# power.net
KiCad netlist of a schematic drawn in Altium Designer
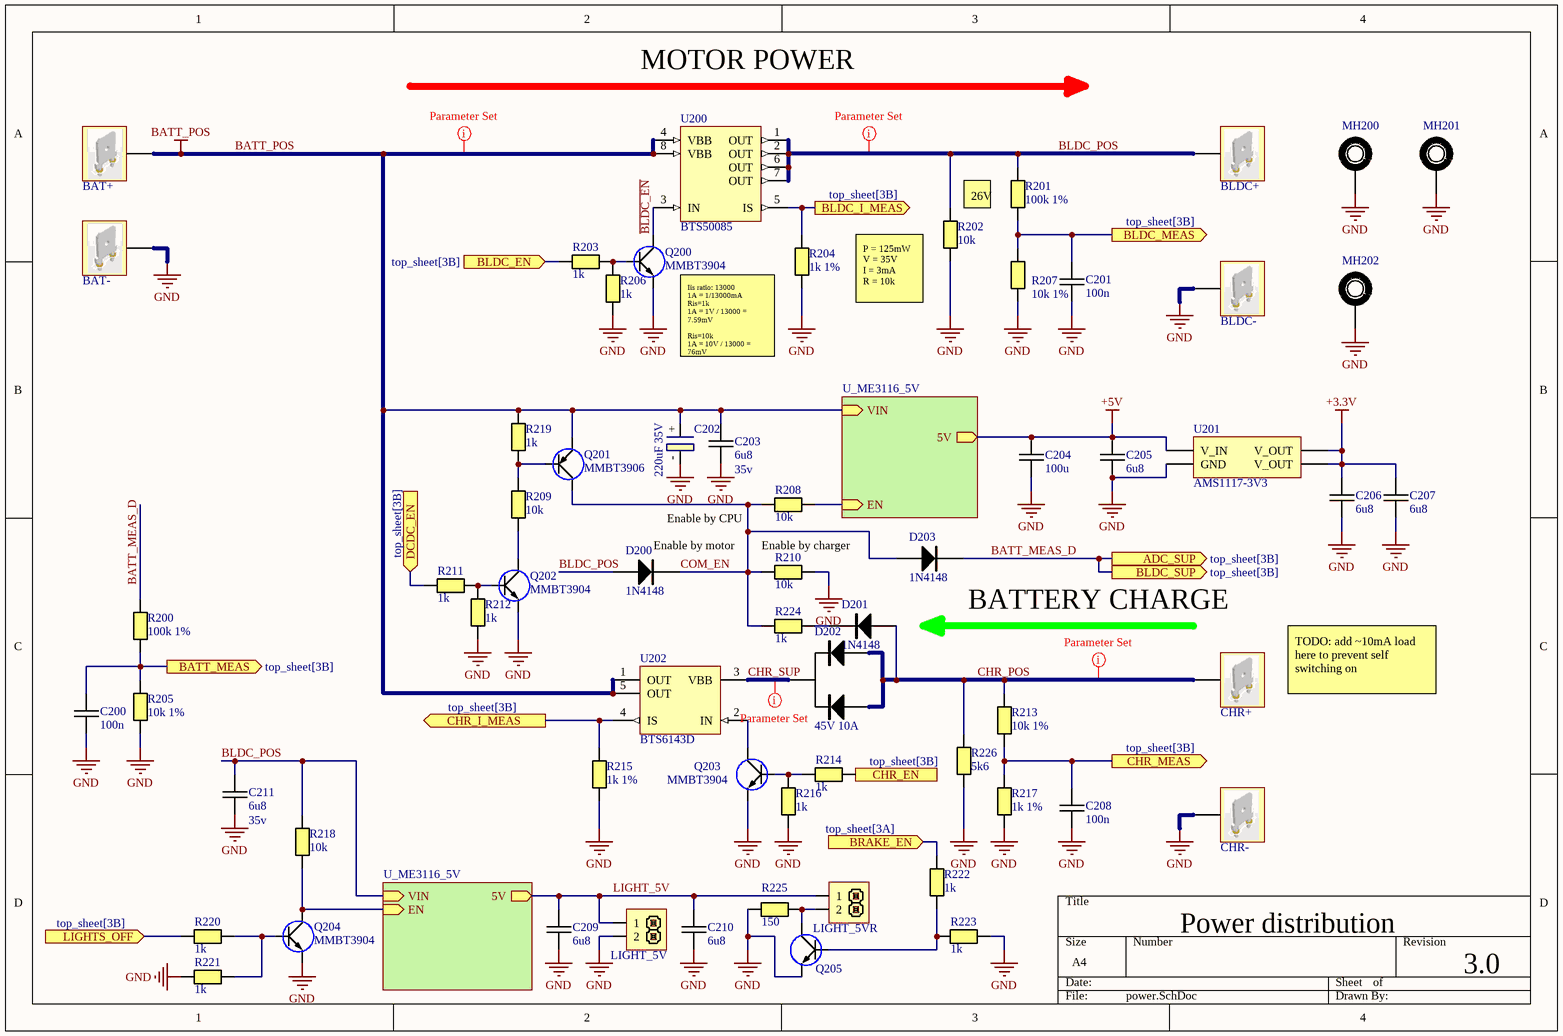
[diagram p0: power.SchDoc]

(export (version "E")
  (design (tool "Eeschema 10.0.6"))
  (components
    (comp (ref "BAT+")
      (value "Crimp 6.3 single PCB")
      (footprint "Crimp 6.3mm single PCB")
      (description "Straight Mount Angle PCB Tab Terminal")
      (libsource (lib "Connectors") (part "Crimp 6.3 single PCB"))
    )
    (comp (ref "BAT-")
      (value "Crimp 6.3 single PCB")
      (footprint "Crimp 6.3mm single PCB")
      (description "Straight Mount Angle PCB Tab Terminal")
      (libsource (lib "Connectors") (part "Crimp 6.3 single PCB"))
    )
    (comp (ref "BLDC+")
      (value "Crimp 6.3 single PCB")
      (footprint "Crimp 6.3mm single PCB")
      (description "Straight Mount Angle PCB Tab Terminal")
      (libsource (lib "") (part "Crimp 6.3 single PCB_1"))
    )
    (comp (ref "BLDC-")
      (value "Crimp 6.3 single PCB")
      (footprint "Crimp 6.3mm single PCB")
      (description "Straight Mount Angle PCB Tab Terminal")
      (libsource (lib "") (part "Crimp 6.3 single PCB_1"))
    )
    (comp (ref "C200")
      (value "100n")
      (footprint "CAPC0603(1608)55_N")
      (description "Ceramic capacitor Medium density")
      (libsource (lib "Discrete") (part "Capacitor M"))
    )
    (comp (ref "C201")
      (value "100n")
      (footprint "CAPC0603(1608)55_N")
      (description "Ceramic capacitor Medium density")
      (libsource (lib "Discrete") (part "Capacitor M"))
    )
    (comp (ref "C202")
      (value "220uF 35V")
      (footprint "10x10.5 Capacitor")
      (description "Capacitor Electrolitic")
      (libsource (lib "Discrete") (part "Capacitor Electrolitic"))
    )
    (comp (ref "C203")
      (value "6u8")
      (footprint "CAPC0805(2012)75_N")
      (description "Ceramic capacitor Medium density")
      (fields (field (name "VMAX") "35v"))
      (libsource (lib "Discrete") (part "Capacitor M"))
    )
    (comp (ref "C204")
      (value "100u")
      (footprint "CAPC1206(3216)75_N")
      (description "Ceramic capacitor Medium density")
      (libsource (lib "Discrete") (part "Capacitor M"))
    )
    (comp (ref "C205")
      (value "6u8")
      (footprint "CAPC0805(2012)75_N")
      (description "Ceramic capacitor Medium density")
      (libsource (lib "Discrete") (part "Capacitor M"))
    )
    (comp (ref "C206")
      (value "6u8")
      (footprint "CAPC0805(2012)75_N")
      (description "Ceramic capacitor Medium density")
      (libsource (lib "Discrete") (part "Capacitor M"))
    )
    (comp (ref "C207")
      (value "6u8")
      (footprint "CAPC0805(2012)75_N")
      (description "Ceramic capacitor Medium density")
      (libsource (lib "Discrete") (part "Capacitor M"))
    )
    (comp (ref "C208")
      (value "100n")
      (footprint "CAPC0603(1608)55_N")
      (description "Ceramic capacitor Medium density")
      (libsource (lib "Discrete") (part "Capacitor M"))
    )
    (comp (ref "C209")
      (value "6u8")
      (footprint "CAPC0805(2012)75_N")
      (description "Ceramic capacitor Medium density")
      (libsource (lib "Discrete") (part "Capacitor M"))
    )
    (comp (ref "C210")
      (value "6u8")
      (footprint "CAPC0805(2012)75_N")
      (description "Ceramic capacitor Medium density")
      (libsource (lib "Discrete") (part "Capacitor M"))
    )
    (comp (ref "C211")
      (value "6u8")
      (footprint "CAPC0805(2012)75_N")
      (description "Ceramic capacitor Medium density")
      (fields (field (name "VMAX") "35v"))
      (libsource (lib "Discrete") (part "Capacitor M"))
    )
    (comp (ref "CHR+")
      (value "Crimp 6.3 single PCB")
      (footprint "Crimp 6.3mm single PCB")
      (description "Straight Mount Angle PCB Tab Terminal")
      (libsource (lib "") (part "Crimp 6.3 single PCB_1"))
    )
    (comp (ref "CHR-")
      (value "Crimp 6.3 single PCB")
      (footprint "Crimp 6.3mm single PCB")
      (description "Straight Mount Angle PCB Tab Terminal")
      (libsource (lib "") (part "Crimp 6.3 single PCB_1"))
    )
    (comp (ref "CN200")
      (value "PIN HEADER 1x2")
      (footprint "XH2.54 2P")
      (description "LIGHT_5V")
      (fields (field (name "PARAMETER 1") "LIGHT_5V"))
      (libsource (lib "Connectors") (part "PIN HEADER 2.54 1x2"))
    )
    (comp (ref "CN201")
      (value "PIN HEADER 1x2")
      (footprint "XH2.54 2P")
      (description "LIGHT_5V")
      (fields (field (name "PARAMETER 1") "LIGHT_5VR"))
      (libsource (lib "Connectors") (part "PIN HEADER 2.54 1x2"))
    )
    (comp (ref "D200")
      (value "1N4148")
      (footprint "SOD80")
      (description "Small Signal Fast Switching Diodes")
      (libsource (lib "Diodes") (part "1N4148"))
    )
    (comp (ref "D201")
      (value "1N4148")
      (footprint "SOD80")
      (description "Small Signal Fast Switching Diodes")
      (libsource (lib "Diodes") (part "1N4148"))
    )
    (comp (ref "D202")
      (value "45V 10A")
      (footprint "DPAK")
      (description "Power schottky rectifier")
      (libsource (lib "Diodes") (part "STPS1045B"))
    )
    (comp (ref "D203")
      (value "1N4148")
      (footprint "SOD80")
      (description "Small Signal Fast Switching Diodes")
      (libsource (lib "Diodes") (part "1N4148"))
    )
    (comp (ref "MH200")
      (value "Mounting Hole")
      (footprint "MH_M3")
      (libsource (lib "Connectors") (part "Mounting Hole"))
    )
    (comp (ref "MH201")
      (value "Mounting Hole")
      (footprint "MH_M3")
      (libsource (lib "Connectors") (part "Mounting Hole"))
    )
    (comp (ref "MH202")
      (value "Mounting Hole")
      (footprint "MH_M3")
      (libsource (lib "Connectors") (part "Mounting Hole"))
    )
    (comp (ref "Q200")
      (value "MMBT3904")
      (footprint "SOT23")
      (description "NPN General Purpose Transistor")
      (libsource (lib "Transistors") (part "2N3904"))
    )
    (comp (ref "Q201")
      (value "MMBT3906")
      (footprint "SOT23")
      (description "PNP General Purpose Transistor")
      (libsource (lib "Transistors") (part "2N3906"))
    )
    (comp (ref "Q202")
      (value "MMBT3904")
      (footprint "SOT23")
      (description "NPN General Purpose Transistor")
      (libsource (lib "Transistors") (part "2N3904"))
    )
    (comp (ref "Q203")
      (value "MMBT3904")
      (footprint "SOT23")
      (description "NPN General Purpose Transistor")
      (libsource (lib "Transistors") (part "2N3904"))
    )
    (comp (ref "Q204")
      (value "MMBT3904")
      (footprint "SOT23")
      (description "NPN General Purpose Transistor")
      (libsource (lib "Transistors") (part "2N3904"))
    )
    (comp (ref "Q205")
      (value "MMBT3904")
      (footprint "SOT23")
      (description "NPN General Purpose Transistor")
      (libsource (lib "Transistors") (part "2N3904"))
    )
    (comp (ref "R200")
      (value "100k 1%")
      (footprint "RESC0603(1608)_N")
      (description "Resistor Medium Density")
      (libsource (lib "Discrete") (part "Resistor M"))
    )
    (comp (ref "R201")
      (value "100k 1%")
      (footprint "RESC0603(1608)_N")
      (description "Resistor Medium Density")
      (libsource (lib "Discrete") (part "Resistor M"))
    )
    (comp (ref "R202")
      (value "10k")
      (footprint "RESC0805(2012)_N")
      (description "Resistor Medium Density")
      (libsource (lib "Discrete") (part "Resistor M"))
    )
    (comp (ref "R203")
      (value "1k")
      (footprint "RESC0603(1608)_N")
      (description "Resistor Medium Density")
      (libsource (lib "") (part "Resistor M_1"))
    )
    (comp (ref "R204")
      (value "1k 1%")
      (footprint "RESC0603(1608)_N")
      (description "Resistor Medium Density")
      (libsource (lib "Discrete") (part "Resistor M"))
    )
    (comp (ref "R205")
      (value "10k 1%")
      (footprint "RESC0603(1608)_N")
      (description "Resistor Medium Density")
      (libsource (lib "Discrete") (part "Resistor M"))
    )
    (comp (ref "R206")
      (value "1k")
      (footprint "RESC0603(1608)_N")
      (description "Resistor Medium Density")
      (libsource (lib "Discrete") (part "Resistor M"))
    )
    (comp (ref "R207")
      (value "10k 1%")
      (footprint "RESC0603(1608)_N")
      (description "Resistor Medium Density")
      (libsource (lib "Discrete") (part "Resistor M"))
    )
    (comp (ref "R208")
      (value "10k")
      (footprint "RESC0603(1608)_N")
      (description "Resistor Medium Density")
      (libsource (lib "") (part "Resistor M_2"))
    )
    (comp (ref "R209")
      (value "10k")
      (footprint "RESC0603(1608)_N")
      (description "Resistor Medium Density")
      (libsource (lib "") (part "Resistor M_3"))
    )
    (comp (ref "R210")
      (value "10k")
      (footprint "RESC0603(1608)_N")
      (description "Resistor Medium Density")
      (libsource (lib "") (part "Resistor M_1"))
    )
    (comp (ref "R211")
      (value "1k")
      (footprint "RESC0603(1608)_N")
      (description "Resistor Medium Density")
      (libsource (lib "") (part "Resistor M_1"))
    )
    (comp (ref "R212")
      (value "1k")
      (footprint "RESC0603(1608)_N")
      (description "Resistor Medium Density")
      (libsource (lib "Discrete") (part "Resistor M"))
    )
    (comp (ref "R213")
      (value "10k 1%")
      (footprint "RESC0603(1608)_N")
      (description "Resistor Medium Density")
      (libsource (lib "Discrete") (part "Resistor M"))
    )
    (comp (ref "R214")
      (value "1k")
      (footprint "RESC0603(1608)_N")
      (description "Resistor Medium Density")
      (libsource (lib "") (part "Resistor M_3"))
    )
    (comp (ref "R215")
      (value "1k 1%")
      (footprint "RESC0603(1608)_N")
      (description "Resistor Medium Density")
      (libsource (lib "Discrete") (part "Resistor M"))
    )
    (comp (ref "R216")
      (value "1k")
      (footprint "RESC0603(1608)_N")
      (description "Resistor Medium Density")
      (libsource (lib "Discrete") (part "Resistor M"))
    )
    (comp (ref "R217")
      (value "1k 1%")
      (footprint "RESC0603(1608)_N")
      (description "Resistor Medium Density")
      (libsource (lib "Discrete") (part "Resistor M"))
    )
    (comp (ref "R218")
      (value "10k")
      (footprint "RESC0603(1608)_N")
      (description "Resistor Medium Density")
      (libsource (lib "Discrete") (part "Resistor M"))
    )
    (comp (ref "R219")
      (value "1k")
      (footprint "RESC0603(1608)_N")
      (description "Resistor Medium Density")
      (libsource (lib "Discrete") (part "Resistor M"))
    )
    (comp (ref "R220")
      (value "1k")
      (footprint "RESC0603(1608)_N")
      (description "Resistor Medium Density")
      (libsource (lib "") (part "Resistor M_2"))
    )
    (comp (ref "R221")
      (value "1k")
      (footprint "RESC0603(1608)_N")
      (description "Resistor Medium Density")
      (libsource (lib "") (part "Resistor M_2"))
    )
    (comp (ref "R222")
      (value "1k")
      (footprint "RESC0603(1608)_N")
      (description "Resistor Medium Density")
      (libsource (lib "") (part "Resistor M_2"))
    )
    (comp (ref "R223")
      (value "1k")
      (footprint "RESC0603(1608)_N")
      (description "Resistor Medium Density")
      (libsource (lib "") (part "Resistor M_2"))
    )
    (comp (ref "R224")
      (value "1k")
      (footprint "RESC0603(1608)_N")
      (description "Resistor Medium Density")
      (libsource (lib "") (part "Resistor M_2"))
    )
    (comp (ref "R225")
      (value "150")
      (footprint "RESC0805(2012)_N")
      (description "Resistor Medium Density")
      (libsource (lib "") (part "Resistor M_1"))
    )
    (comp (ref "R226")
      (value "5k6")
      (footprint "RESC1206(3216)_N")
      (description "Resistor Medium Density")
      (libsource (lib "Discrete") (part "Resistor M"))
    )
    (comp (ref "U200")
      (value "BTS50085")
      (footprint "PG-TO220-7-4")
      (description "Smart Highside High Current Power Switch")
      (libsource (lib "Switches") (part "BTS50085-1TMA"))
    )
    (comp (ref "U201")
      (value "AMS1117-3V3")
      (footprint "SOT229P700X180-4N")
      (description "800mA LDO  15V max")
      (libsource (lib "VoltageRegulators") (part "AMS1117"))
    )
    (comp (ref "U202")
      (value "BTS6143D")
      (footprint "ITO252-5-11_M")
      (fields (field (name "MANUFACTURER") "Infineon"))
      (libsource (lib "Switches") (part "BTS6143D"))
    )
  )
  (nets
    (net (code "1") (name "+3.3V") (class "Default")
      (node (ref "C206") (pin "1") (pinfunction "1_1") (pintype "passive"))
      (node (ref "C207") (pin "1") (pinfunction "1_1") (pintype "passive"))
      (node (ref "U201") (pin "2") (pinfunction "V_OUT_2") (pintype "passive"))
      (node (ref "U201") (pin "4") (pinfunction "V_OUT_4") (pintype "passive"))
    )
    (net (code "2") (name "+5V") (class "Default")
      (node (ref "C204") (pin "1") (pinfunction "1_1") (pintype "passive"))
      (node (ref "C205") (pin "1") (pinfunction "1_1") (pintype "passive"))
      (node (ref "U201") (pin "3") (pinfunction "V_IN_3") (pintype "passive"))
    )
    (net (code "3") (name "/BATT_MEAS") (class "Default")
      (node (ref "C200") (pin "1") (pinfunction "1_1") (pintype "passive"))
      (node (ref "R200") (pin "1") (pinfunction "1_1") (pintype "passive"))
      (node (ref "R205") (pin "2") (pinfunction "2_2") (pintype "passive"))
    )
    (net (code "4") (name "/BATT_MEAS_D") (class "Default")
      (node (ref "D203") (pin "2") (pinfunction "K_2") (pintype "passive"))
      (node (ref "R200") (pin "2") (pinfunction "2_2") (pintype "passive"))
    )
    (net (code "5") (name "/BLDC_EN") (class "Default")
      (node (ref "R203") (pin "1") (pinfunction "1_1") (pintype "passive"))
    )
    (net (code "6") (name "/BLDC_I_MEAS") (class "Default")
      (node (ref "R204") (pin "2") (pinfunction "2_2") (pintype "passive"))
      (node (ref "U200") (pin "5") (pinfunction "IS_5") (pintype "output"))
    )
    (net (code "7") (name "/BLDC_MEAS") (class "Default")
      (node (ref "C201") (pin "1") (pinfunction "1_1") (pintype "passive"))
      (node (ref "R201") (pin "1") (pinfunction "1_1") (pintype "passive"))
      (node (ref "R207") (pin "2") (pinfunction "2_2") (pintype "passive"))
    )
    (net (code "8") (name "/BLDC_POS") (class "Default")
      (node (ref "BLDC+") (pin "1") (pintype "passive"))
      (node (ref "C211") (pin "1") (pinfunction "1_1") (pintype "passive"))
      (node (ref "D200") (pin "1") (pinfunction "A_1") (pintype "passive"))
      (node (ref "R201") (pin "2") (pinfunction "2_2") (pintype "passive"))
      (node (ref "R202") (pin "2") (pinfunction "2_2") (pintype "passive"))
      (node (ref "R218") (pin "2") (pinfunction "2_2") (pintype "passive"))
      (node (ref "U200") (pin "1") (pinfunction "OUT_1") (pintype "output"))
      (node (ref "U200") (pin "2") (pinfunction "OUT_2") (pintype "output"))
      (node (ref "U200") (pin "6") (pinfunction "OUT_6") (pintype "output"))
      (node (ref "U200") (pin "7") (pinfunction "OUT_7") (pintype "output"))
    )
    (net (code "9") (name "/BRAKE_EN") (class "Default")
      (node (ref "R222") (pin "1") (pinfunction "1_1") (pintype "passive"))
    )
    (net (code "10") (name "/CHR_EN") (class "Default")
      (node (ref "R214") (pin "1") (pinfunction "1_1") (pintype "passive"))
    )
    (net (code "11") (name "/CHR_I_MEAS") (class "Default")
      (node (ref "R215") (pin "2") (pinfunction "2_2") (pintype "passive"))
      (node (ref "U202") (pin "4") (pinfunction "IS_4") (pintype "output"))
    )
    (net (code "12") (name "/CHR_MEAS") (class "Default")
      (node (ref "C208") (pin "1") (pinfunction "1_1") (pintype "passive"))
      (node (ref "R213") (pin "1") (pinfunction "1_1") (pintype "passive"))
      (node (ref "R217") (pin "2") (pinfunction "2_2") (pintype "passive"))
    )
    (net (code "13") (name "/CHR_POS") (class "Default")
      (node (ref "CHR+") (pin "1") (pintype "passive"))
      (node (ref "D201") (pin "1") (pinfunction "A_1") (pintype "passive"))
      (node (ref "D202") (pin "1") (pinfunction "A1_1") (pintype "passive"))
      (node (ref "D202") (pin "3") (pinfunction "A2_3") (pintype "passive"))
      (node (ref "R213") (pin "2") (pinfunction "2_2") (pintype "passive"))
      (node (ref "R226") (pin "2") (pinfunction "2_2") (pintype "passive"))
    )
    (net (code "14") (name "/CHR_SUP") (class "Default")
      (node (ref "D202") (pin "2") (pinfunction "K_2") (pintype "passive"))
      (node (ref "U202") (pin "3") (pinfunction "VBB_3") (pintype "power_in"))
    )
    (net (code "15") (name "/COM_EN") (class "Default")
      (node (ref "D200") (pin "2") (pinfunction "K_2") (pintype "passive"))
      (node (ref "D203") (pin "1") (pinfunction "A_1") (pintype "passive"))
      (node (ref "Q201") (pin "3") (pinfunction "C_3") (pintype "passive"))
      (node (ref "R208") (pin "2") (pinfunction "2_2") (pintype "passive"))
      (node (ref "R210") (pin "1") (pinfunction "1_1") (pintype "passive"))
      (node (ref "R224") (pin "2") (pinfunction "2_2") (pintype "passive"))
    )
    (net (code "16") (name "/DCDC_EN") (class "Default")
      (node (ref "R211") (pin "1") (pinfunction "1_1") (pintype "passive"))
    )
    (net (code "17") (name "/EN") (class "Default")
      (node (ref "Q204") (pin "3") (pinfunction "C_3") (pintype "passive"))
      (node (ref "R218") (pin "1") (pinfunction "1_1") (pintype "passive"))
    )
    (net (code "18") (name "/EN_1") (class "Default")
      (node (ref "R208") (pin "1") (pinfunction "1_1") (pintype "passive"))
    )
    (net (code "19") (name "/LIGHTS_OFF") (class "Default")
      (node (ref "R220") (pin "2") (pinfunction "2_2") (pintype "passive"))
    )
    (net (code "20") (name "/LIGHT_5V") (class "Default")
      (node (ref "C209") (pin "1") (pinfunction "1_1") (pintype "passive"))
      (node (ref "C210") (pin "1") (pinfunction "1_1") (pintype "passive"))
      (node (ref "CN200") (pin "1") (pinfunction "1_1") (pintype "passive"))
      (node (ref "CN201") (pin "1") (pinfunction "1_1") (pintype "passive"))
    )
    (net (code "21") (name "/~{BLDC_EN}") (class "Default")
      (node (ref "Q200") (pin "3") (pinfunction "C_3") (pintype "passive"))
      (node (ref "U200") (pin "3") (pinfunction "IN_3") (pintype "input"))
    )
    (net (code "22") (name "BATT_POS") (class "Default")
      (node (ref "BAT+") (pin "1") (pintype "passive"))
      (node (ref "C202") (pin "+") (pinfunction "+_+") (pintype "passive"))
      (node (ref "C203") (pin "2") (pinfunction "2_2") (pintype "passive"))
      (node (ref "Q201") (pin "2") (pinfunction "E_2") (pintype "passive"))
      (node (ref "R219") (pin "2") (pinfunction "2_2") (pintype "passive"))
      (node (ref "U200") (pin "4") (pinfunction "VBB_4") (pintype "input"))
      (node (ref "U200") (pin "8") (pinfunction "VBB_8") (pintype "input"))
      (node (ref "U202") (pin "1") (pinfunction "OUT_1") (pintype "tri_state"))
      (node (ref "U202") (pin "5") (pinfunction "OUT_5") (pintype "tri_state"))
    )
    (net (code "23") (name "GND") (class "Default")
      (node (ref "BAT-") (pin "1") (pintype "passive"))
      (node (ref "BLDC-") (pin "1") (pintype "passive"))
      (node (ref "C200") (pin "2") (pinfunction "2_2") (pintype "passive"))
      (node (ref "C201") (pin "2") (pinfunction "2_2") (pintype "passive"))
      (node (ref "C202") (pin "-") (pinfunction "-_-") (pintype "passive"))
      (node (ref "C203") (pin "1") (pinfunction "1_1") (pintype "passive"))
      (node (ref "C204") (pin "2") (pinfunction "2_2") (pintype "passive"))
      (node (ref "C205") (pin "2") (pinfunction "2_2") (pintype "passive"))
      (node (ref "C206") (pin "2") (pinfunction "2_2") (pintype "passive"))
      (node (ref "C207") (pin "2") (pinfunction "2_2") (pintype "passive"))
      (node (ref "C208") (pin "2") (pinfunction "2_2") (pintype "passive"))
      (node (ref "C209") (pin "2") (pinfunction "2_2") (pintype "passive"))
      (node (ref "C210") (pin "2") (pinfunction "2_2") (pintype "passive"))
      (node (ref "C211") (pin "2") (pinfunction "2_2") (pintype "passive"))
      (node (ref "CHR-") (pin "1") (pintype "passive"))
      (node (ref "CN200") (pin "2") (pinfunction "2_2") (pintype "passive"))
      (node (ref "MH200") (pin "1") (pintype "passive"))
      (node (ref "MH201") (pin "1") (pintype "passive"))
      (node (ref "MH202") (pin "1") (pintype "passive"))
      (node (ref "Q200") (pin "2") (pinfunction "E_2") (pintype "passive"))
      (node (ref "Q202") (pin "2") (pinfunction "E_2") (pintype "passive"))
      (node (ref "Q203") (pin "2") (pinfunction "E_2") (pintype "passive"))
      (node (ref "Q204") (pin "2") (pinfunction "E_2") (pintype "passive"))
      (node (ref "Q205") (pin "2") (pinfunction "E_2") (pintype "passive"))
      (node (ref "R202") (pin "1") (pinfunction "1_1") (pintype "passive"))
      (node (ref "R204") (pin "1") (pinfunction "1_1") (pintype "passive"))
      (node (ref "R205") (pin "1") (pinfunction "1_1") (pintype "passive"))
      (node (ref "R206") (pin "1") (pinfunction "1_1") (pintype "passive"))
      (node (ref "R207") (pin "1") (pinfunction "1_1") (pintype "passive"))
      (node (ref "R210") (pin "2") (pinfunction "2_2") (pintype "passive"))
      (node (ref "R212") (pin "1") (pinfunction "1_1") (pintype "passive"))
      (node (ref "R215") (pin "1") (pinfunction "1_1") (pintype "passive"))
      (node (ref "R216") (pin "1") (pinfunction "1_1") (pintype "passive"))
      (node (ref "R217") (pin "1") (pinfunction "1_1") (pintype "passive"))
      (node (ref "R221") (pin "2") (pinfunction "2_2") (pintype "passive"))
      (node (ref "R223") (pin "1") (pinfunction "1_1") (pintype "passive"))
      (node (ref "R225") (pin "1") (pinfunction "1_1") (pintype "passive"))
      (node (ref "R226") (pin "1") (pinfunction "1_1") (pintype "passive"))
      (node (ref "U201") (pin "1") (pinfunction "GND_1") (pintype "passive"))
    )
    (net (code "24") (name "Net-(D201-K)") (class "Default")
      (node (ref "D201") (pin "2") (pinfunction "K_2") (pintype "passive"))
      (node (ref "R224") (pin "1") (pinfunction "1_1") (pintype "passive"))
    )
    (net (code "25") (name "Net-(Q200-B)") (class "Default")
      (node (ref "Q200") (pin "1") (pinfunction "B_1") (pintype "passive"))
      (node (ref "R203") (pin "2") (pinfunction "2_2") (pintype "passive"))
      (node (ref "R206") (pin "2") (pinfunction "2_2") (pintype "passive"))
    )
    (net (code "26") (name "Net-(Q201-B)") (class "Default")
      (node (ref "Q201") (pin "1") (pinfunction "B_1") (pintype "passive"))
      (node (ref "R209") (pin "1") (pinfunction "1_1") (pintype "passive"))
      (node (ref "R219") (pin "1") (pinfunction "1_1") (pintype "passive"))
    )
    (net (code "27") (name "Net-(Q202-B)") (class "Default")
      (node (ref "Q202") (pin "1") (pinfunction "B_1") (pintype "passive"))
      (node (ref "R211") (pin "2") (pinfunction "2_2") (pintype "passive"))
      (node (ref "R212") (pin "2") (pinfunction "2_2") (pintype "passive"))
    )
    (net (code "28") (name "Net-(Q202-C)") (class "Default")
      (node (ref "Q202") (pin "3") (pinfunction "C_3") (pintype "passive"))
      (node (ref "R209") (pin "2") (pinfunction "2_2") (pintype "passive"))
    )
    (net (code "29") (name "Net-(Q203-B)") (class "Default")
      (node (ref "Q203") (pin "1") (pinfunction "B_1") (pintype "passive"))
      (node (ref "R214") (pin "2") (pinfunction "2_2") (pintype "passive"))
      (node (ref "R216") (pin "2") (pinfunction "2_2") (pintype "passive"))
    )
    (net (code "30") (name "Net-(Q203-C)") (class "Default")
      (node (ref "Q203") (pin "3") (pinfunction "C_3") (pintype "passive"))
      (node (ref "U202") (pin "2") (pinfunction "IN_2") (pintype "input"))
    )
    (net (code "31") (name "Net-(Q204-B)") (class "Default")
      (node (ref "Q204") (pin "1") (pinfunction "B_1") (pintype "passive"))
      (node (ref "R220") (pin "1") (pinfunction "1_1") (pintype "passive"))
      (node (ref "R221") (pin "1") (pinfunction "1_1") (pintype "passive"))
    )
    (net (code "32") (name "Net-(Q205-B)") (class "Default")
      (node (ref "Q205") (pin "1") (pinfunction "B_1") (pintype "passive"))
      (node (ref "R222") (pin "2") (pinfunction "2_2") (pintype "passive"))
      (node (ref "R223") (pin "2") (pinfunction "2_2") (pintype "passive"))
    )
    (net (code "33") (name "Net-(Q205-C)") (class "Default")
      (node (ref "CN201") (pin "2") (pinfunction "2_2") (pintype "passive"))
      (node (ref "Q205") (pin "3") (pinfunction "C_3") (pintype "passive"))
      (node (ref "R225") (pin "2") (pinfunction "2_2") (pintype "passive"))
    )
  )
)
